# mainBord_real.net
KiCad netlist of a schematic drawn in Altium Designer
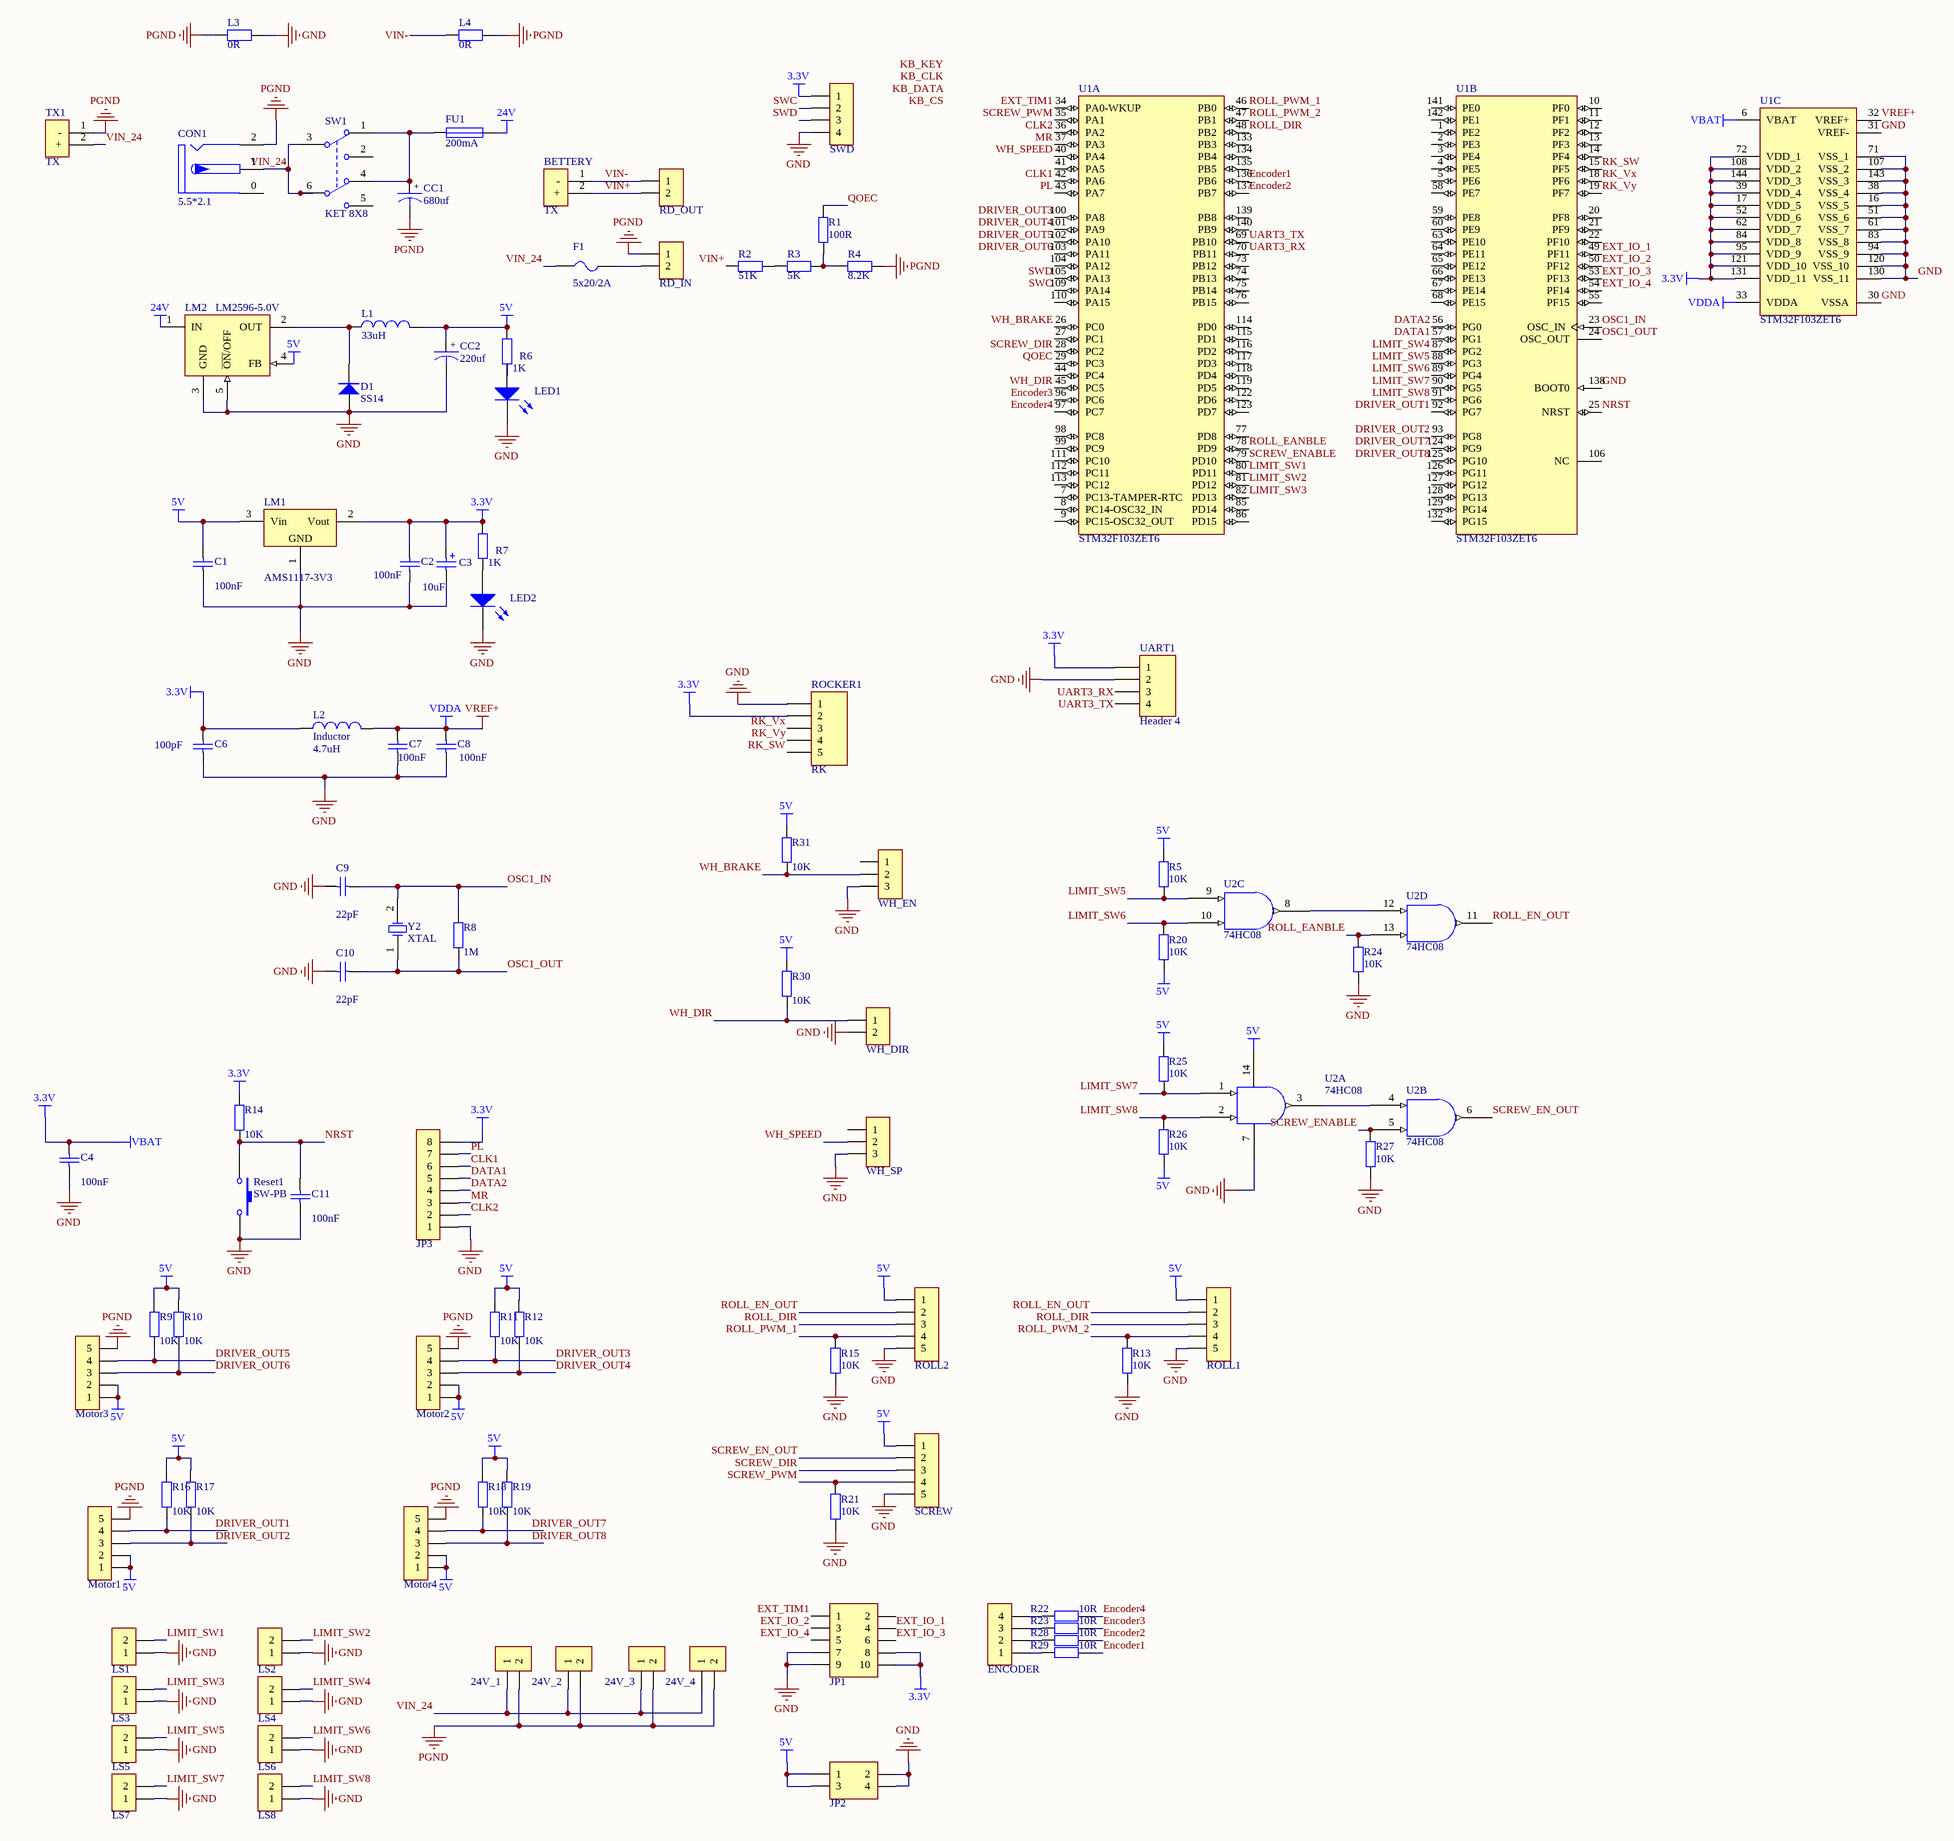
[diagram p0: mainBord_real.SchDoc]

(export (version "E")
  (design (tool "Eeschema 10.0.6"))
  (components
    (comp (ref "24V_1")
      (value "HDR-1X2")
      (footprint "KF2EDGK5.0-LI-2P")
      (description "2P接插件")
      (fields (field (name "版权归属") "源创客"))
      (libsource (lib "接插件") (part "Header 2"))
    )
    (comp (ref "24V_2")
      (value "HDR-1X2")
      (footprint "KF2EDGK5.0-LI-2P")
      (description "2P接插件")
      (fields (field (name "版权归属") "源创客"))
      (libsource (lib "接插件") (part "Header 2"))
    )
    (comp (ref "24V_3")
      (value "HDR-1X2")
      (footprint "KF2EDGK5.0-LI-2P")
      (description "2P接插件")
      (fields (field (name "版权归属") "源创客"))
      (libsource (lib "接插件") (part "Header 2"))
    )
    (comp (ref "24V_4")
      (value "HDR-1X2")
      (footprint "KF2EDGK5.0-LI-2P")
      (description "2P接插件")
      (fields (field (name "版权归属") "源创客"))
      (libsource (lib "接插件") (part "Header 2"))
    )
    (comp (ref "BETTERY") (value "TX") (footprint "TX") (libsource (lib "接头") (part "T型插头")))
    (comp (ref "C1")
      (value "100nF")
      (footprint "C 0805_L")
      (description "Capacitor")
      (fields (field (name "Comment") "100nf") (field (name "PUBLISHER") "Altium Limited"))
      (libsource (lib "Miscellaneous Devices") (part "Cap"))
    )
    (comp (ref "C2")
      (value "100nF")
      (footprint "C 0805_L")
      (description "Capacitor")
      (fields (field (name "Comment") "100nf") (field (name "PUBLISHER") "Altium Limited"))
      (libsource (lib "Miscellaneous Devices") (part "Cap"))
    )
    (comp (ref "C3")
      (value "10uF")
      (footprint "CD A(3216)")
      (description "Polarized Capacitor (Axial)")
      (fields (field (name "Comment") "10uf") (field (name "PUBLISHER") "Altium Limited"))
      (libsource (lib "Miscellaneous Devices") (part "Cap Pol2"))
    )
    (comp (ref "C4")
      (value "100nF")
      (footprint "C 0805_L")
      (description "Capacitor")
      (fields (field (name "Comment") "100nf") (field (name "PUBLISHER") "Altium Limited"))
      (libsource (lib "Miscellaneous Devices") (part "Cap"))
    )
    (comp (ref "C6")
      (value "100pF")
      (footprint "C 0805_L")
      (description "Capacitor")
      (fields (field (name "Comment") "100nf") (field (name "PUBLISHER") "Altium Limited"))
      (libsource (lib "Miscellaneous Devices") (part "Cap"))
    )
    (comp (ref "C7")
      (value "100nF")
      (footprint "C 0805_L")
      (description "Capacitor")
      (fields (field (name "Comment") "100nf") (field (name "PUBLISHER") "Altium Limited"))
      (libsource (lib "Miscellaneous Devices") (part "Cap"))
    )
    (comp (ref "C8")
      (value "100nF")
      (footprint "C 0805_L")
      (description "Capacitor")
      (fields (field (name "Comment") "100nf") (field (name "PUBLISHER") "Altium Limited"))
      (libsource (lib "Miscellaneous Devices") (part "Cap"))
    )
    (comp (ref "C9")
      (value "22pF")
      (footprint "C 0805_L")
      (description "Capacitor")
      (fields (field (name "Comment") "22pf") (field (name "PUBLISHER") "Altium Limited"))
      (libsource (lib "Miscellaneous Devices") (part "Cap"))
    )
    (comp (ref "C10")
      (value "22pF")
      (footprint "C 0805_L")
      (description "Capacitor")
      (fields (field (name "Comment") "22pf") (field (name "PUBLISHER") "Altium Limited"))
      (libsource (lib "Miscellaneous Devices") (part "Cap"))
    )
    (comp (ref "C11")
      (value "100nF")
      (footprint "C 0805_L")
      (description "Capacitor")
      (fields (field (name "Comment") "100nf") (field (name "PUBLISHER") "Altium Limited"))
      (libsource (lib "Miscellaneous Devices") (part "Cap"))
    )
    (comp (ref "CC1")
      (value "680uf")
      (footprint "CM F(10*10.2)")
      (description "贴片铝解电容")
      (libsource (lib "常用器件") (part "CAP-T"))
    )
    (comp (ref "CC2")
      (value "220uf")
      (footprint "CM E(8*10.2)")
      (description "贴片铝解电容")
      (libsource (lib "常用器件") (part "CAP-T"))
    )
    (comp (ref "CON1")
      (value "5.5*2.1")
      (footprint "DC-005")
      (description "带屏蔽DC电源接口")
      (fields (field (name "版权归属") "源创客"))
      (libsource (lib "4.1   - 接口类") (part "DC-005P"))
    )
    (comp (ref "D1")
      (value "SS14")
      (footprint "SMA")
      (description "肖特基二极管")
      (fields (field (name "版权归属") "源创客"))
      (libsource (lib "8.1   - 二极管-整流桥") (part "SS14"))
    )
    (comp (ref "ENCODER")
      (value "HDR-1X4")
      (footprint "HDR2.54-LI-4P")
      (description "4P接插件")
      (fields (field (name "版权归属") "源创客"))
      (libsource (lib "4.5   - 接插件-脚距2.54") (part "Header 4"))
    )
    (comp (ref "F1")
      (value "5x20/2A")
      (footprint "FU 5x20")
      (description "直插保险丝")
      (fields (field (name "版权归属") "源创客"))
      (libsource (lib "10.1 - 保险丝-晶振") (part "FU DIP"))
    )
    (comp (ref "FU1") (value "200mA") (footprint "R 1206-HP_M") (libsource (lib "常用器件") (part "FUSE")))
    (comp (ref "JP1")
      (value "Header 5X2")
      (footprint "HDR2.54-LI-2x5P")
      (description "5*2P接插件")
      (fields (field (name "版权归属") "源创客"))
      (libsource (lib "4.5   - 接插件-脚距2.54") (part "Header 5X2"))
    )
    (comp (ref "JP2")
      (value "Header2X2")
      (footprint "HDR2.54-LI-2x2P")
      (description "2*2P接插件")
      (fields (field (name "版权归属") "源创客"))
      (libsource (lib "4.5   - 接插件-脚距2.54") (part "Header 2X2"))
    )
    (comp (ref "JP3")
      (value "HDR-1X8")
      (footprint "XH2.54-LI-8P")
      (description "8P接插件")
      (fields (field (name "版权归属") "源创客"))
      (libsource (lib "4.5   - 接插件-脚距2.54") (part "Header 8"))
    )
    (comp (ref "L1")
      (value "33uH")
      (footprint "CDRH125")
      (description "Inductor")
      (fields
        (field (name "MANUFACTURER") "Generic Components")
        (field (name "PUBLISHER") "Altium Hobart Technology Centre")
      )
      (libsource (lib "常用器件") (part "Inductor"))
    )
    (comp (ref "L2")
      (value "Inductor")
      (footprint "L 0805")
      (fields (field (name "ALTIUM_VALUE") "4.7uH") (field (name "PUBLISHER") "Altium Limited"))
      (libsource (lib "Miscellaneous Devices") (part "Inductor"))
    )
    (comp (ref "L3")
      (value "0R")
      (footprint "R 0805_L")
      (description "Resistor")
      (fields (field (name "Comment") "1K") (field (name "PUBLISHER") "Altium Limited"))
      (libsource (lib "") (part "Res2_1"))
    )
    (comp (ref "L4")
      (value "0R")
      (footprint "R 0805_L")
      (description "Resistor")
      (fields (field (name "Comment") "1K") (field (name "PUBLISHER") "Altium Limited"))
      (libsource (lib "") (part "Res2_1"))
    )
    (comp (ref "LED1")
      (value "LED2")
      (footprint "LED 0805B")
      (description "Typical RED, GREEN, YELLOW, AMBER GaAs LED")
      (fields (field (name "PUBLISHER") "Altium Limited"))
      (libsource (lib "Miscellaneous Devices") (part "LED2"))
    )
    (comp (ref "LED2")
      (value "LED2")
      (footprint "LED 0805B")
      (description "Typical RED, GREEN, YELLOW, AMBER GaAs LED")
      (fields (field (name "PUBLISHER") "Altium Limited"))
      (libsource (lib "Miscellaneous Devices") (part "LED2"))
    )
    (comp (ref "LM1")
      (value "AMS1117-3V3")
      (footprint "SOT223_L")
      (description "三端稳压芯片")
      (fields (field (name "版权归属") "源创客"))
      (libsource (lib "1.3   - 电源类芯片") (part "AMS1117"))
    )
    (comp (ref "LM2")
      (value "LM2596-5.0V")
      (footprint "TO263-5A")
      (description "DC降压芯片")
      (fields (field (name "版权归属") "源创客"))
      (libsource (lib "1.3   - 电源类芯片") (part "LM2596-5.0"))
    )
    (comp (ref "LS1")
      (value "HDR-1X2")
      (footprint "XH2.54-LI-2P")
      (description "2P接插件")
      (fields (field (name "版权归属") "源创客"))
      (libsource (lib "4.5   - 接插件-脚距2.54") (part "Header 2"))
    )
    (comp (ref "LS2")
      (value "HDR-1X2")
      (footprint "XH2.54-LI-2P")
      (description "2P接插件")
      (fields (field (name "版权归属") "源创客"))
      (libsource (lib "4.5   - 接插件-脚距2.54") (part "Header 2"))
    )
    (comp (ref "LS3")
      (value "HDR-1X2")
      (footprint "XH2.54-LI-2P")
      (description "2P接插件")
      (fields (field (name "版权归属") "源创客"))
      (libsource (lib "4.5   - 接插件-脚距2.54") (part "Header 2"))
    )
    (comp (ref "LS4")
      (value "HDR-1X2")
      (footprint "XH2.54-LI-2P")
      (description "2P接插件")
      (fields (field (name "版权归属") "源创客"))
      (libsource (lib "4.5   - 接插件-脚距2.54") (part "Header 2"))
    )
    (comp (ref "LS5")
      (value "HDR-1X2")
      (footprint "XH2.54-LI-2P")
      (description "2P接插件")
      (fields (field (name "版权归属") "源创客"))
      (libsource (lib "4.5   - 接插件-脚距2.54") (part "Header 2"))
    )
    (comp (ref "LS6")
      (value "HDR-1X2")
      (footprint "XH2.54-LI-2P")
      (description "2P接插件")
      (fields (field (name "版权归属") "源创客"))
      (libsource (lib "4.5   - 接插件-脚距2.54") (part "Header 2"))
    )
    (comp (ref "LS7")
      (value "HDR-1X2")
      (footprint "XH2.54-LI-2P")
      (description "2P接插件")
      (fields (field (name "版权归属") "源创客"))
      (libsource (lib "4.5   - 接插件-脚距2.54") (part "Header 2"))
    )
    (comp (ref "LS8")
      (value "HDR-1X2")
      (footprint "XH2.54-LI-2P")
      (description "2P接插件")
      (fields (field (name "版权归属") "源创客"))
      (libsource (lib "4.5   - 接插件-脚距2.54") (part "Header 2"))
    )
    (comp (ref "Motor1")
      (value "HDR-1X5")
      (footprint "KF128-3.81-5P")
      (description "5P接插件")
      (fields (field (name "版权归属") "源创客"))
      (libsource (lib "接插件") (part "Header 5"))
    )
    (comp (ref "Motor2")
      (value "HDR-1X5")
      (footprint "KF128-3.81-5P")
      (description "5P接插件")
      (fields (field (name "版权归属") "源创客"))
      (libsource (lib "接插件") (part "Header 5"))
    )
    (comp (ref "Motor3")
      (value "HDR-1X5")
      (footprint "KF128-3.81-5P")
      (description "5P接插件")
      (fields (field (name "版权归属") "源创客"))
      (libsource (lib "接插件") (part "Header 5"))
    )
    (comp (ref "Motor4")
      (value "HDR-1X5")
      (footprint "KF128-3.81-5P")
      (description "5P接插件")
      (fields (field (name "版权归属") "源创客"))
      (libsource (lib "接插件") (part "Header 5"))
    )
    (comp (ref "R1")
      (value "100R")
      (footprint "R 0805_L")
      (description "Resistor")
      (fields (field (name "Comment") "1K") (field (name "PUBLISHER") "Altium Limited"))
      (libsource (lib "") (part "Res2_3"))
    )
    (comp (ref "R2")
      (value "51K")
      (footprint "R 0805_L")
      (description "Resistor")
      (fields (field (name "Comment") "1K") (field (name "PUBLISHER") "Altium Limited"))
      (libsource (lib "") (part "Res2_1"))
    )
    (comp (ref "R3")
      (value "5K")
      (footprint "R 0805_L")
      (description "Resistor")
      (fields (field (name "Comment") "1K") (field (name "PUBLISHER") "Altium Limited"))
      (libsource (lib "") (part "Res2_1"))
    )
    (comp (ref "R4")
      (value "8.2K")
      (footprint "R 0805_L")
      (description "Resistor")
      (fields (field (name "Comment") "1K") (field (name "PUBLISHER") "Altium Limited"))
      (libsource (lib "") (part "Res2_1"))
    )
    (comp (ref "R5")
      (value "10K")
      (footprint "R 0805_L")
      (description "Resistor")
      (fields (field (name "Comment") "5K") (field (name "PUBLISHER") "Altium Limited"))
      (libsource (lib "Miscellaneous Devices") (part "Res2"))
    )
    (comp (ref "R6")
      (value "1K")
      (footprint "R 0805_L")
      (description "Resistor")
      (fields (field (name "PUBLISHER") "Altium Limited"))
      (libsource (lib "Miscellaneous Devices") (part "Res2"))
    )
    (comp (ref "R7")
      (value "1K")
      (footprint "R 0805_L")
      (description "Resistor")
      (fields (field (name "PUBLISHER") "Altium Limited"))
      (libsource (lib "Miscellaneous Devices") (part "Res2"))
    )
    (comp (ref "R8")
      (value "1M")
      (footprint "R 0805_L")
      (description "Resistor")
      (fields (field (name "PUBLISHER") "Altium Limited"))
      (libsource (lib "Miscellaneous Devices") (part "Res2"))
    )
    (comp (ref "R9")
      (value "10K")
      (footprint "R 0805_L")
      (description "Resistor")
      (fields (field (name "Comment") "1K") (field (name "PUBLISHER") "Altium Limited"))
      (libsource (lib "Miscellaneous Devices") (part "Res2"))
    )
    (comp (ref "R10")
      (value "10K")
      (footprint "R 0805_L")
      (description "Resistor")
      (fields (field (name "Comment") "1K") (field (name "PUBLISHER") "Altium Limited"))
      (libsource (lib "Miscellaneous Devices") (part "Res2"))
    )
    (comp (ref "R11")
      (value "10K")
      (footprint "R 0805_L")
      (description "Resistor")
      (fields (field (name "Comment") "1K") (field (name "PUBLISHER") "Altium Limited"))
      (libsource (lib "Miscellaneous Devices") (part "Res2"))
    )
    (comp (ref "R12")
      (value "10K")
      (footprint "R 0805_L")
      (description "Resistor")
      (fields (field (name "Comment") "1K") (field (name "PUBLISHER") "Altium Limited"))
      (libsource (lib "Miscellaneous Devices") (part "Res2"))
    )
    (comp (ref "R13")
      (value "10K")
      (footprint "R 0805_L")
      (description "Resistor")
      (fields (field (name "Comment") "1K") (field (name "PUBLISHER") "Altium Limited"))
      (libsource (lib "") (part "Res2_3"))
    )
    (comp (ref "R14")
      (value "10K")
      (footprint "R 0805_L")
      (description "Resistor")
      (fields (field (name "Comment") "1K") (field (name "PUBLISHER") "Altium Limited"))
      (libsource (lib "Miscellaneous Devices") (part "Res2"))
    )
    (comp (ref "R15")
      (value "10K")
      (footprint "R 0805_L")
      (description "Resistor")
      (fields (field (name "Comment") "1K") (field (name "PUBLISHER") "Altium Limited"))
      (libsource (lib "") (part "Res2_3"))
    )
    (comp (ref "R16")
      (value "10K")
      (footprint "R 0805_L")
      (description "Resistor")
      (fields (field (name "Comment") "1K") (field (name "PUBLISHER") "Altium Limited"))
      (libsource (lib "Miscellaneous Devices") (part "Res2"))
    )
    (comp (ref "R17")
      (value "10K")
      (footprint "R 0805_L")
      (description "Resistor")
      (fields (field (name "Comment") "1K") (field (name "PUBLISHER") "Altium Limited"))
      (libsource (lib "Miscellaneous Devices") (part "Res2"))
    )
    (comp (ref "R18")
      (value "10K")
      (footprint "R 0805_L")
      (description "Resistor")
      (fields (field (name "Comment") "1K") (field (name "PUBLISHER") "Altium Limited"))
      (libsource (lib "Miscellaneous Devices") (part "Res2"))
    )
    (comp (ref "R19")
      (value "10K")
      (footprint "R 0805_L")
      (description "Resistor")
      (fields (field (name "Comment") "1K") (field (name "PUBLISHER") "Altium Limited"))
      (libsource (lib "Miscellaneous Devices") (part "Res2"))
    )
    (comp (ref "R20")
      (value "10K")
      (footprint "R 0805_L")
      (description "Resistor")
      (fields (field (name "Comment") "5K") (field (name "PUBLISHER") "Altium Limited"))
      (libsource (lib "Miscellaneous Devices") (part "Res2"))
    )
    (comp (ref "R21")
      (value "10K")
      (footprint "R 0805_L")
      (description "Resistor")
      (fields (field (name "Comment") "1K") (field (name "PUBLISHER") "Altium Limited"))
      (libsource (lib "") (part "Res2_3"))
    )
    (comp (ref "R22")
      (value "10R")
      (footprint "R 0805_L")
      (description "Resistor")
      (fields (field (name "Comment") "1K") (field (name "PUBLISHER") "Altium Limited"))
      (libsource (lib "") (part "Res2_2"))
    )
    (comp (ref "R23")
      (value "10R")
      (footprint "R 0805_L")
      (description "Resistor")
      (fields (field (name "Comment") "1K") (field (name "PUBLISHER") "Altium Limited"))
      (libsource (lib "") (part "Res2_2"))
    )
    (comp (ref "R24")
      (value "10K")
      (footprint "R 0805_L")
      (description "Resistor")
      (fields (field (name "Comment") "1K") (field (name "PUBLISHER") "Altium Limited"))
      (libsource (lib "Miscellaneous Devices") (part "Res2"))
    )
    (comp (ref "R25")
      (value "10K")
      (footprint "R 0805_L")
      (description "Resistor")
      (fields (field (name "Comment") "5K") (field (name "PUBLISHER") "Altium Limited"))
      (libsource (lib "Miscellaneous Devices") (part "Res2"))
    )
    (comp (ref "R26")
      (value "10K")
      (footprint "R 0805_L")
      (description "Resistor")
      (fields (field (name "Comment") "5K") (field (name "PUBLISHER") "Altium Limited"))
      (libsource (lib "Miscellaneous Devices") (part "Res2"))
    )
    (comp (ref "R27")
      (value "10K")
      (footprint "R 0805_L")
      (description "Resistor")
      (fields (field (name "Comment") "1K") (field (name "PUBLISHER") "Altium Limited"))
      (libsource (lib "Miscellaneous Devices") (part "Res2"))
    )
    (comp (ref "R28")
      (value "10R")
      (footprint "R 0805_L")
      (description "Resistor")
      (fields (field (name "Comment") "1K") (field (name "PUBLISHER") "Altium Limited"))
      (libsource (lib "") (part "Res2_2"))
    )
    (comp (ref "R29")
      (value "10R")
      (footprint "R 0805_L")
      (description "Resistor")
      (fields (field (name "Comment") "1K") (field (name "PUBLISHER") "Altium Limited"))
      (libsource (lib "") (part "Res2_2"))
    )
    (comp (ref "R30")
      (value "10K")
      (footprint "R 0805_L")
      (description "Resistor")
      (fields (field (name "Comment") "1K") (field (name "PUBLISHER") "Altium Limited"))
      (libsource (lib "Miscellaneous Devices") (part "Res2"))
    )
    (comp (ref "R31")
      (value "10K")
      (footprint "R 0805_L")
      (description "Resistor")
      (fields (field (name "Comment") "1K") (field (name "PUBLISHER") "Altium Limited"))
      (libsource (lib "Miscellaneous Devices") (part "Res2"))
    )
    (comp (ref "RD_IN")
      (value "HDR-1X2")
      (footprint "KF2EDGK5.0-WI-2P")
      (description "2P接插件")
      (fields (field (name "版权归属") "源创客"))
      (libsource (lib "") (part "Header 2_1"))
    )
    (comp (ref "RD_OUT")
      (value "HDR-1X2")
      (footprint "KF2EDGK5.0-WI-2P")
      (description "2P接插件")
      (fields (field (name "版权归属") "源创客"))
      (libsource (lib "") (part "Header 2_1"))
    )
    (comp (ref "Reset1")
      (value "SW-PB")
      (footprint "switch_1")
      (description "Switch")
      (fields (field (name "PUBLISHER") "Altium Limited"))
      (libsource (lib "Miscellaneous Devices") (part "SW-PB"))
    )
    (comp (ref "ROCKER1")
      (value "RK")
      (footprint "HDR2.54-M-LI-5P")
      (description "Header, 5-Pin")
      (fields (field (name "PUBLISHER") "Altium Limited"))
      (libsource (lib "Miscellaneous Connectors") (part "MHDR1X5"))
    )
    (comp (ref "ROLL1")
      (value "HDR-1X5")
      (footprint "XH2.54-LI-5P")
      (description "5P接插件")
      (fields (field (name "版权归属") "源创客"))
      (libsource (lib "4.5   - 接插件-脚距2.54") (part "Header 5"))
    )
    (comp (ref "ROLL2")
      (value "HDR-1X5")
      (footprint "XH2.54-LI-5P")
      (description "5P接插件")
      (fields (field (name "版权归属") "源创客"))
      (libsource (lib "4.5   - 接插件-脚距2.54") (part "Header 5"))
    )
    (comp (ref "SCREW")
      (value "HDR-1X5")
      (footprint "XH2.54-LI-5P")
      (description "5P接插件")
      (fields (field (name "版权归属") "源创客"))
      (libsource (lib "4.5   - 接插件-脚距2.54") (part "Header 5"))
    )
    (comp (ref "SW1")
      (value "KET 8X8")
      (footprint "KFT DIP-8X8")
      (description "8*8自锁开关")
      (fields (field (name "版权归属") "源创客"))
      (libsource (lib "5.1   - 按键-开关") (part "KET 8X8"))
    )
    (comp (ref "SWD")
      (value "HDR-1X4")
      (footprint "HDR2.54-LI-4P")
      (description "4P接插件")
      (fields (field (name "版权归属") "源创客"))
      (libsource (lib "") (part "Header 4_1"))
    )
    (comp (ref "TX1") (value "TX") (footprint "TX") (libsource (lib "接头") (part "T型插头")))
    (comp (ref "U1")
      (value "STM32F103ZET6")
      (footprint "STM-LQFP144_N")
      (libsource (lib "STMicroelectronics STM32 F1") (part "STM32F103ZET6"))
    )
    (comp (ref "U2") (value "74HC08") (footprint "SOP14_N") (libsource (lib "逻辑门器件") (part "74HC08")))
    (comp (ref "UART1")
      (value "Header 4")
      (footprint "HDR2.54-LI-4P")
      (description "Header, 4-Pin")
      (fields (field (name "PUBLISHER") "Altium Limited"))
      (libsource (lib "Miscellaneous Connectors") (part "Header 4"))
    )
    (comp (ref "WH_DIR")
      (value "HDR-1X2")
      (footprint "XH2.54-LI-2P")
      (description "2P接插件")
      (fields (field (name "版权归属") "源创客"))
      (libsource (lib "") (part "Header 2_1"))
    )
    (comp (ref "WH_EN")
      (value "HDR-1X3")
      (footprint "XH2.54-LI-3P")
      (description "3P接插件")
      (fields (field (name "版权归属") "源创客"))
      (libsource (lib "4.5   - 接插件-脚距2.54") (part "Header 3"))
    )
    (comp (ref "WH_SP")
      (value "HDR-1X3")
      (footprint "XH2.54-LI-3P")
      (description "3P接插件")
      (fields (field (name "版权归属") "源创客"))
      (libsource (lib "4.5   - 接插件-脚距2.54") (part "Header 3"))
    )
    (comp (ref "Y2")
      (value "XTAL")
      (footprint "OSC HC-49S")
      (description "Crystal Oscillator")
      (fields (field (name "PUBLISHER") "Altium Limited"))
      (libsource (lib "Miscellaneous Devices") (part "XTAL"))
    )
  )
  (nets
    (net (code "1") (name "/CLK1") (class "Default")
      (node (ref "JP3") (pin "6") (pinfunction "6_6") (pintype "passive"))
      (node (ref "U1") (pin "42") (pinfunction "PA6_42") (pintype "bidirectional"))
    )
    (net (code "2") (name "/CLK2") (class "Default")
      (node (ref "JP3") (pin "2") (pinfunction "2_2") (pintype "passive"))
      (node (ref "U1") (pin "36") (pinfunction "PA2_36") (pintype "bidirectional"))
    )
    (net (code "3") (name "/DATA1") (class "Default")
      (node (ref "JP3") (pin "5") (pinfunction "5_5") (pintype "passive"))
      (node (ref "U1") (pin "57") (pinfunction "PG1_57") (pintype "bidirectional"))
    )
    (net (code "4") (name "/DATA2") (class "Default")
      (node (ref "JP3") (pin "4") (pinfunction "4_4") (pintype "passive"))
      (node (ref "U1") (pin "56") (pinfunction "PG0_56") (pintype "bidirectional"))
    )
    (net (code "5") (name "/DRIVER_OUT1") (class "Default")
      (node (ref "Motor1") (pin "4") (pinfunction "4_4") (pintype "passive"))
      (node (ref "R16") (pin "1") (pinfunction "1_1") (pintype "passive"))
      (node (ref "U1") (pin "92") (pinfunction "PG7_92") (pintype "bidirectional"))
    )
    (net (code "6") (name "/DRIVER_OUT2") (class "Default")
      (node (ref "Motor1") (pin "3") (pinfunction "3_3") (pintype "passive"))
      (node (ref "R17") (pin "1") (pinfunction "1_1") (pintype "passive"))
      (node (ref "U1") (pin "93") (pinfunction "PG8_93") (pintype "bidirectional"))
    )
    (net (code "7") (name "/DRIVER_OUT3") (class "Default")
      (node (ref "Motor2") (pin "4") (pinfunction "4_4") (pintype "passive"))
      (node (ref "R11") (pin "1") (pinfunction "1_1") (pintype "passive"))
      (node (ref "U1") (pin "100") (pinfunction "PA8_100") (pintype "bidirectional"))
    )
    (net (code "8") (name "/DRIVER_OUT4") (class "Default")
      (node (ref "Motor2") (pin "3") (pinfunction "3_3") (pintype "passive"))
      (node (ref "R12") (pin "1") (pinfunction "1_1") (pintype "passive"))
      (node (ref "U1") (pin "101") (pinfunction "PA9_101") (pintype "bidirectional"))
    )
    (net (code "9") (name "/DRIVER_OUT5") (class "Default")
      (node (ref "Motor3") (pin "4") (pinfunction "4_4") (pintype "passive"))
      (node (ref "R9") (pin "1") (pinfunction "1_1") (pintype "passive"))
      (node (ref "U1") (pin "102") (pinfunction "PA10_102") (pintype "bidirectional"))
    )
    (net (code "10") (name "/DRIVER_OUT6") (class "Default")
      (node (ref "Motor3") (pin "3") (pinfunction "3_3") (pintype "passive"))
      (node (ref "R10") (pin "1") (pinfunction "1_1") (pintype "passive"))
      (node (ref "U1") (pin "103") (pinfunction "PA11_103") (pintype "bidirectional"))
    )
    (net (code "11") (name "/DRIVER_OUT7") (class "Default")
      (node (ref "Motor4") (pin "4") (pinfunction "4_4") (pintype "passive"))
      (node (ref "R18") (pin "1") (pinfunction "1_1") (pintype "passive"))
      (node (ref "U1") (pin "124") (pinfunction "PG9_124") (pintype "bidirectional"))
    )
    (net (code "12") (name "/DRIVER_OUT8") (class "Default")
      (node (ref "Motor4") (pin "3") (pinfunction "3_3") (pintype "passive"))
      (node (ref "R19") (pin "1") (pinfunction "1_1") (pintype "passive"))
      (node (ref "U1") (pin "125") (pinfunction "PG10_125") (pintype "bidirectional"))
    )
    (net (code "13") (name "/EXT_IO_1") (class "Default")
      (node (ref "JP1") (pin "4") (pinfunction "4_4") (pintype "passive"))
      (node (ref "U1") (pin "49") (pinfunction "PF11_49") (pintype "bidirectional"))
    )
    (net (code "14") (name "/EXT_IO_2") (class "Default")
      (node (ref "JP1") (pin "3") (pinfunction "3_3") (pintype "passive"))
      (node (ref "U1") (pin "50") (pinfunction "PF12_50") (pintype "bidirectional"))
    )
    (net (code "15") (name "/EXT_IO_3") (class "Default")
      (node (ref "JP1") (pin "6") (pinfunction "6_6") (pintype "passive"))
      (node (ref "U1") (pin "53") (pinfunction "PF13_53") (pintype "bidirectional"))
    )
    (net (code "16") (name "/EXT_IO_4") (class "Default")
      (node (ref "JP1") (pin "5") (pinfunction "5_5") (pintype "passive"))
      (node (ref "U1") (pin "54") (pinfunction "PF14_54") (pintype "bidirectional"))
    )
    (net (code "17") (name "/EXT_TIM1") (class "Default")
      (node (ref "JP1") (pin "1") (pinfunction "1_1") (pintype "passive"))
      (node (ref "U1") (pin "34") (pinfunction "PA0-WKUP_34") (pintype "bidirectional"))
    )
    (net (code "18") (name "/Encoder1") (class "Default")
      (node (ref "R29") (pin "2") (pinfunction "2_2") (pintype "passive"))
      (node (ref "U1") (pin "136") (pinfunction "PB6_136") (pintype "bidirectional"))
    )
    (net (code "19") (name "/Encoder2") (class "Default")
      (node (ref "R28") (pin "2") (pinfunction "2_2") (pintype "passive"))
      (node (ref "U1") (pin "137") (pinfunction "PB7_137") (pintype "bidirectional"))
    )
    (net (code "20") (name "/Encoder3") (class "Default")
      (node (ref "R23") (pin "2") (pinfunction "2_2") (pintype "passive"))
      (node (ref "U1") (pin "96") (pinfunction "PC6_96") (pintype "bidirectional"))
    )
    (net (code "21") (name "/Encoder4") (class "Default")
      (node (ref "R22") (pin "2") (pinfunction "2_2") (pintype "passive"))
      (node (ref "U1") (pin "97") (pinfunction "PC7_97") (pintype "bidirectional"))
    )
    (net (code "26") (name "/LIMIT_SW1") (class "Default")
      (node (ref "LS1") (pin "2") (pinfunction "2_2") (pintype "passive"))
      (node (ref "U1") (pin "80") (pinfunction "PD11_80") (pintype "bidirectional"))
    )
    (net (code "27") (name "/LIMIT_SW2") (class "Default")
      (node (ref "LS2") (pin "2") (pinfunction "2_2") (pintype "passive"))
      (node (ref "U1") (pin "81") (pinfunction "PD12_81") (pintype "bidirectional"))
    )
    (net (code "28") (name "/LIMIT_SW3") (class "Default")
      (node (ref "LS3") (pin "2") (pinfunction "2_2") (pintype "passive"))
      (node (ref "U1") (pin "82") (pinfunction "PD13_82") (pintype "bidirectional"))
    )
    (net (code "29") (name "/LIMIT_SW4") (class "Default")
      (node (ref "LS4") (pin "2") (pinfunction "2_2") (pintype "passive"))
      (node (ref "U1") (pin "87") (pinfunction "PG2_87") (pintype "bidirectional"))
    )
    (net (code "30") (name "/LIMIT_SW5") (class "Default")
      (node (ref "LS5") (pin "2") (pinfunction "2_2") (pintype "passive"))
      (node (ref "R5") (pin "1") (pinfunction "1_1") (pintype "passive"))
      (node (ref "U1") (pin "88") (pinfunction "PG3_88") (pintype "bidirectional"))
      (node (ref "U2") (pin "9") (pintype "input"))
    )
    (net (code "31") (name "/LIMIT_SW6") (class "Default")
      (node (ref "LS6") (pin "2") (pinfunction "2_2") (pintype "passive"))
      (node (ref "R20") (pin "2") (pinfunction "2_2") (pintype "passive"))
      (node (ref "U1") (pin "89") (pinfunction "PG4_89") (pintype "bidirectional"))
      (node (ref "U2") (pin "10") (pintype "input"))
    )
    (net (code "32") (name "/LIMIT_SW7") (class "Default")
      (node (ref "LS7") (pin "2") (pinfunction "2_2") (pintype "passive"))
      (node (ref "R25") (pin "1") (pinfunction "1_1") (pintype "passive"))
      (node (ref "U1") (pin "90") (pinfunction "PG5_90") (pintype "bidirectional"))
      (node (ref "U2") (pin "1") (pintype "input"))
    )
    (net (code "33") (name "/LIMIT_SW8") (class "Default")
      (node (ref "LS8") (pin "2") (pinfunction "2_2") (pintype "passive"))
      (node (ref "R26") (pin "2") (pinfunction "2_2") (pintype "passive"))
      (node (ref "U1") (pin "91") (pinfunction "PG6_91") (pintype "bidirectional"))
      (node (ref "U2") (pin "2") (pintype "input"))
    )
    (net (code "34") (name "/MR") (class "Default")
      (node (ref "JP3") (pin "3") (pinfunction "3_3") (pintype "passive"))
      (node (ref "U1") (pin "37") (pinfunction "PA3_37") (pintype "bidirectional"))
    )
    (net (code "35") (name "/NRST") (class "Default")
      (node (ref "C11") (pin "1") (pinfunction "1_1") (pintype "passive"))
      (node (ref "R14") (pin "1") (pinfunction "1_1") (pintype "passive"))
      (node (ref "Reset1") (pin "1") (pinfunction "1_1") (pintype "passive"))
      (node (ref "U1") (pin "25") (pinfunction "NRST_25") (pintype "bidirectional"))
    )
    (net (code "36") (name "/OSC1_IN") (class "Default")
      (node (ref "C9") (pin "1") (pinfunction "1_1") (pintype "passive"))
      (node (ref "R8") (pin "2") (pinfunction "2_2") (pintype "passive"))
      (node (ref "U1") (pin "23") (pinfunction "OSC_IN_23") (pintype "input"))
      (node (ref "Y2") (pin "2") (pinfunction "OSC2_2") (pintype "passive"))
    )
    (net (code "37") (name "/OSC1_OUT") (class "Default")
      (node (ref "C10") (pin "1") (pinfunction "1_1") (pintype "passive"))
      (node (ref "R8") (pin "1") (pinfunction "1_1") (pintype "passive"))
      (node (ref "U1") (pin "24") (pinfunction "OSC_OUT_24") (pintype "passive"))
      (node (ref "Y2") (pin "1") (pinfunction "OSC1_1") (pintype "passive"))
    )
    (net (code "38") (name "/PL") (class "Default")
      (node (ref "JP3") (pin "7") (pinfunction "7_7") (pintype "passive"))
      (node (ref "U1") (pin "43") (pinfunction "PA7_43") (pintype "bidirectional"))
    )
    (net (code "39") (name "/QOEC") (class "Default")
      (node (ref "R1") (pin "1") (pinfunction "1_1") (pintype "passive"))
      (node (ref "U1") (pin "29") (pinfunction "PC3_29") (pintype "bidirectional"))
    )
    (net (code "40") (name "/RK_SW") (class "Default")
      (node (ref "ROCKER1") (pin "5") (pinfunction "5_5") (pintype "passive"))
      (node (ref "U1") (pin "15") (pinfunction "PF5_15") (pintype "bidirectional"))
    )
    (net (code "41") (name "/RK_Vx") (class "Default")
      (node (ref "ROCKER1") (pin "3") (pinfunction "3_3") (pintype "passive"))
      (node (ref "U1") (pin "18") (pinfunction "PF6_18") (pintype "bidirectional"))
    )
    (net (code "42") (name "/RK_Vy") (class "Default")
      (node (ref "ROCKER1") (pin "4") (pinfunction "4_4") (pintype "passive"))
      (node (ref "U1") (pin "19") (pinfunction "PF7_19") (pintype "bidirectional"))
    )
    (net (code "43") (name "/ROLL_DIR") (class "Default")
      (node (ref "ROLL1") (pin "3") (pinfunction "3_3") (pintype "passive"))
      (node (ref "ROLL2") (pin "3") (pinfunction "3_3") (pintype "passive"))
      (node (ref "U1") (pin "48") (pinfunction "PB2_48") (pintype "bidirectional"))
    )
    (net (code "44") (name "/ROLL_EANBLE") (class "Default")
      (node (ref "R24") (pin "2") (pinfunction "2_2") (pintype "passive"))
      (node (ref "U1") (pin "78") (pinfunction "PD9_78") (pintype "bidirectional"))
      (node (ref "U2") (pin "13") (pintype "input"))
    )
    (net (code "45") (name "/ROLL_EN_OUT") (class "Default")
      (node (ref "ROLL1") (pin "2") (pinfunction "2_2") (pintype "passive"))
      (node (ref "ROLL2") (pin "2") (pinfunction "2_2") (pintype "passive"))
      (node (ref "U2") (pin "11") (pintype "output"))
    )
    (net (code "46") (name "/ROLL_PWM_1") (class "Default")
      (node (ref "R15") (pin "1") (pinfunction "1_1") (pintype "passive"))
      (node (ref "ROLL2") (pin "4") (pinfunction "4_4") (pintype "passive"))
      (node (ref "U1") (pin "46") (pinfunction "PB0_46") (pintype "bidirectional"))
    )
    (net (code "47") (name "/ROLL_PWM_2") (class "Default")
      (node (ref "R13") (pin "1") (pinfunction "1_1") (pintype "passive"))
      (node (ref "ROLL1") (pin "4") (pinfunction "4_4") (pintype "passive"))
      (node (ref "U1") (pin "47") (pinfunction "PB1_47") (pintype "bidirectional"))
    )
    (net (code "48") (name "/SCREW_DIR") (class "Default")
      (node (ref "SCREW") (pin "3") (pinfunction "3_3") (pintype "passive"))
      (node (ref "U1") (pin "28") (pinfunction "PC2_28") (pintype "bidirectional"))
    )
    (net (code "49") (name "/SCREW_ENABLE") (class "Default")
      (node (ref "R27") (pin "2") (pinfunction "2_2") (pintype "passive"))
      (node (ref "U1") (pin "79") (pinfunction "PD10_79") (pintype "bidirectional"))
      (node (ref "U2") (pin "5") (pintype "input"))
    )
    (net (code "50") (name "/SCREW_EN_OUT") (class "Default")
      (node (ref "SCREW") (pin "2") (pinfunction "2_2") (pintype "passive"))
      (node (ref "U2") (pin "6") (pintype "output"))
    )
    (net (code "51") (name "/SCREW_PWM") (class "Default")
      (node (ref "R21") (pin "1") (pinfunction "1_1") (pintype "passive"))
      (node (ref "SCREW") (pin "4") (pinfunction "4_4") (pintype "passive"))
      (node (ref "U1") (pin "35") (pinfunction "PA1_35") (pintype "bidirectional"))
    )
    (net (code "52") (name "/SWC") (class "Default")
      (node (ref "SWD") (pin "2") (pinfunction "2_2") (pintype "passive"))
      (node (ref "U1") (pin "109") (pinfunction "PA14_109") (pintype "bidirectional"))
    )
    (net (code "53") (name "/SWD") (class "Default")
      (node (ref "SWD") (pin "3") (pinfunction "3_3") (pintype "passive"))
      (node (ref "U1") (pin "105") (pinfunction "PA13_105") (pintype "bidirectional"))
    )
    (net (code "54") (name "/UART3_RX") (class "Default")
      (node (ref "U1") (pin "70") (pinfunction "PB11_70") (pintype "bidirectional"))
      (node (ref "UART1") (pin "3") (pinfunction "3_3") (pintype "passive"))
    )
    (net (code "55") (name "/UART3_TX") (class "Default")
      (node (ref "U1") (pin "69") (pinfunction "PB10_69") (pintype "bidirectional"))
      (node (ref "UART1") (pin "4") (pinfunction "4_4") (pintype "passive"))
    )
    (net (code "56") (name "/VIN+") (class "Default")
      (node (ref "BETTERY") (pin "2") (pinfunction "+_2") (pintype "passive"))
      (node (ref "R2") (pin "2") (pinfunction "2_2") (pintype "passive"))
      (node (ref "RD_OUT") (pin "2") (pinfunction "2_2") (pintype "passive"))
    )
    (net (code "57") (name "/VIN-") (class "Default")
      (node (ref "BETTERY") (pin "1") (pinfunction "-_1") (pintype "passive"))
      (node (ref "L4") (pin "2") (pinfunction "2_2") (pintype "passive"))
      (node (ref "RD_OUT") (pin "1") (pinfunction "1_1") (pintype "passive"))
    )
    (net (code "58") (name "/VIN_24") (class "Default")
      (node (ref "24V_1") (pin "1") (pinfunction "1_1") (pintype "passive"))
      (node (ref "24V_2") (pin "1") (pinfunction "1_1") (pintype "passive"))
      (node (ref "24V_3") (pin "1") (pinfunction "1_1") (pintype "passive"))
      (node (ref "24V_4") (pin "1") (pinfunction "1_1") (pintype "passive"))
      (node (ref "CON1") (pin "1") (pintype "power_in"))
      (node (ref "F1") (pin "2") (pinfunction "2_2") (pintype "passive"))
      (node (ref "SW1") (pin "3") (pinfunction "NO1_3") (pintype "passive"))
      (node (ref "SW1") (pin "6") (pinfunction "NC2_6") (pintype "passive"))
      (node (ref "TX1") (pin "2") (pinfunction "+_2") (pintype "passive"))
    )
    (net (code "59") (name "/WH_BRAKE") (class "Default")
      (node (ref "R31") (pin "1") (pinfunction "1_1") (pintype "passive"))
      (node (ref "U1") (pin "26") (pinfunction "PC0_26") (pintype "bidirectional"))
      (node (ref "WH_EN") (pin "2") (pinfunction "2_2") (pintype "passive"))
    )
    (net (code "60") (name "/WH_DIR") (class "Default")
      (node (ref "R30") (pin "1") (pinfunction "1_1") (pintype "passive"))
      (node (ref "U1") (pin "45") (pinfunction "PC5_45") (pintype "bidirectional"))
      (node (ref "WH_DIR") (pin "1") (pinfunction "1_1") (pintype "passive"))
    )
    (net (code "61") (name "/WH_SPEED") (class "Default")
      (node (ref "U1") (pin "40") (pinfunction "PA4_40") (pintype "bidirectional"))
      (node (ref "WH_SP") (pin "2") (pinfunction "2_2") (pintype "passive"))
    )
    (net (code "62") (name "3.3V") (class "Default")
      (node (ref "C2") (pin "2") (pinfunction "2_2") (pintype "passive"))
      (node (ref "C3") (pin "1") (pinfunction "1_1") (pintype "passive"))
      (node (ref "C4") (pin "1") (pinfunction "1_1") (pintype "passive"))
      (node (ref "C6") (pin "2") (pinfunction "2_2") (pintype "passive"))
      (node (ref "JP1") (pin "10") (pinfunction "10_10") (pintype "passive"))
      (node (ref "JP1") (pin "8") (pinfunction "8_8") (pintype "passive"))
      (node (ref "JP3") (pin "8") (pinfunction "8_8") (pintype "passive"))
      (node (ref "L2") (pin "1") (pinfunction "1_1") (pintype "passive"))
      (node (ref "LM1") (pin "2") (pinfunction "Vout_2") (pintype "passive"))
      (node (ref "R14") (pin "2") (pinfunction "2_2") (pintype "passive"))
      (node (ref "R7") (pin "2") (pinfunction "2_2") (pintype "passive"))
      (node (ref "ROCKER1") (pin "2") (pinfunction "2_2") (pintype "passive"))
      (node (ref "SWD") (pin "1") (pinfunction "1_1") (pintype "passive"))
      (node (ref "U1") (pin "108") (pinfunction "VDD_2_108") (pintype "power_in"))
      (node (ref "U1") (pin "121") (pinfunction "VDD_10_121") (pintype "power_in"))
      (node (ref "U1") (pin "131") (pinfunction "VDD_11_131") (pintype "power_in"))
      (node (ref "U1") (pin "144") (pinfunction "VDD_3_144") (pintype "power_in"))
      (node (ref "U1") (pin "17") (pinfunction "VDD_5_17") (pintype "power_in"))
      (node (ref "U1") (pin "39") (pinfunction "VDD_4_39") (pintype "power_in"))
      (node (ref "U1") (pin "52") (pinfunction "VDD_6_52") (pintype "power_in"))
      (node (ref "U1") (pin "6") (pinfunction "VBAT_6") (pintype "power_in"))
      (node (ref "U1") (pin "62") (pinfunction "VDD_7_62") (pintype "power_in"))
      (node (ref "U1") (pin "72") (pinfunction "VDD_1_72") (pintype "power_in"))
      (node (ref "U1") (pin "84") (pinfunction "VDD_8_84") (pintype "power_in"))
      (node (ref "U1") (pin "95") (pinfunction "VDD_9_95") (pintype "power_in"))
      (node (ref "UART1") (pin "1") (pinfunction "1_1") (pintype "passive"))
    )
    (net (code "63") (name "5V") (class "Default")
      (node (ref "C1") (pin "2") (pinfunction "2_2") (pintype "passive"))
      (node (ref "CC2") (pin "1") (pinfunction "1_1") (pintype "passive"))
      (node (ref "JP2") (pin "1") (pinfunction "1_1") (pintype "passive"))
      (node (ref "JP2") (pin "3") (pinfunction "3_3") (pintype "passive"))
      (node (ref "L1") (pin "2") (pinfunction "2_2") (pintype "passive"))
      (node (ref "LM1") (pin "3") (pinfunction "Vin_3") (pintype "passive"))
      (node (ref "LM2") (pin "4") (pinfunction "FB_4") (pintype "input"))
      (node (ref "Motor1") (pin "1") (pinfunction "1_1") (pintype "passive"))
      (node (ref "Motor1") (pin "2") (pinfunction "2_2") (pintype "passive"))
      (node (ref "Motor2") (pin "1") (pinfunction "1_1") (pintype "passive"))
      (node (ref "Motor2") (pin "2") (pinfunction "2_2") (pintype "passive"))
      (node (ref "Motor3") (pin "1") (pinfunction "1_1") (pintype "passive"))
      (node (ref "Motor3") (pin "2") (pinfunction "2_2") (pintype "passive"))
      (node (ref "Motor4") (pin "1") (pinfunction "1_1") (pintype "passive"))
      (node (ref "Motor4") (pin "2") (pinfunction "2_2") (pintype "passive"))
      (node (ref "R10") (pin "2") (pinfunction "2_2") (pintype "passive"))
      (node (ref "R11") (pin "2") (pinfunction "2_2") (pintype "passive"))
      (node (ref "R12") (pin "2") (pinfunction "2_2") (pintype "passive"))
      (node (ref "R16") (pin "2") (pinfunction "2_2") (pintype "passive"))
      (node (ref "R17") (pin "2") (pinfunction "2_2") (pintype "passive"))
      (node (ref "R18") (pin "2") (pinfunction "2_2") (pintype "passive"))
      (node (ref "R19") (pin "2") (pinfunction "2_2") (pintype "passive"))
      (node (ref "R20") (pin "1") (pinfunction "1_1") (pintype "passive"))
      (node (ref "R25") (pin "2") (pinfunction "2_2") (pintype "passive"))
      (node (ref "R26") (pin "1") (pinfunction "1_1") (pintype "passive"))
      (node (ref "R30") (pin "2") (pinfunction "2_2") (pintype "passive"))
      (node (ref "R31") (pin "2") (pinfunction "2_2") (pintype "passive"))
      (node (ref "R5") (pin "2") (pinfunction "2_2") (pintype "passive"))
      (node (ref "R6") (pin "2") (pinfunction "2_2") (pintype "passive"))
      (node (ref "R9") (pin "2") (pinfunction "2_2") (pintype "passive"))
      (node (ref "ROLL1") (pin "1") (pinfunction "1_1") (pintype "passive"))
      (node (ref "ROLL2") (pin "1") (pinfunction "1_1") (pintype "passive"))
      (node (ref "SCREW") (pin "1") (pinfunction "1_1") (pintype "passive"))
      (node (ref "U2") (pin "14") (pinfunction "VCC_14") (pintype "power_in"))
    )
    (net (code "64") (name "24V") (class "Default")
      (node (ref "FU1") (pin "2") (pinfunction "2_2") (pintype "passive"))
      (node (ref "LM2") (pin "1") (pinfunction "IN_1") (pintype "power_in"))
    )
    (net (code "65") (name "GND") (class "Default")
      (node (ref "C1") (pin "1") (pinfunction "1_1") (pintype "passive"))
      (node (ref "C10") (pin "2") (pinfunction "2_2") (pintype "passive"))
      (node (ref "C11") (pin "2") (pinfunction "2_2") (pintype "passive"))
      (node (ref "C2") (pin "1") (pinfunction "1_1") (pintype "passive"))
      (node (ref "C3") (pin "2") (pinfunction "2_2") (pintype "passive"))
      (node (ref "C4") (pin "2") (pinfunction "2_2") (pintype "passive"))
      (node (ref "C6") (pin "1") (pinfunction "1_1") (pintype "passive"))
      (node (ref "C7") (pin "1") (pinfunction "1_1") (pintype "passive"))
      (node (ref "C8") (pin "1") (pinfunction "1_1") (pintype "passive"))
      (node (ref "C9") (pin "2") (pinfunction "2_2") (pintype "passive"))
      (node (ref "CC2") (pin "2") (pinfunction "2_2") (pintype "passive"))
      (node (ref "D1") (pin "1") (pinfunction "A_1") (pintype "passive"))
      (node (ref "JP1") (pin "7") (pinfunction "7_7") (pintype "passive"))
      (node (ref "JP1") (pin "9") (pinfunction "9_9") (pintype "passive"))
      (node (ref "JP2") (pin "2") (pinfunction "2_2") (pintype "passive"))
      (node (ref "JP2") (pin "4") (pinfunction "4_4") (pintype "passive"))
      (node (ref "JP3") (pin "1") (pinfunction "1_1") (pintype "passive"))
      (node (ref "L3") (pin "1") (pinfunction "1_1") (pintype "passive"))
      (node (ref "LED1") (pin "2") (pinfunction "K_2") (pintype "passive"))
      (node (ref "LED2") (pin "2") (pinfunction "K_2") (pintype "passive"))
      (node (ref "LM1") (pin "1") (pinfunction "GND_1") (pintype "passive"))
      (node (ref "LM2") (pin "3") (pinfunction "GND_3") (pintype "power_in"))
      (node (ref "LM2") (pin "5") (pinfunction "~{ON}/OFF_5") (pintype "input"))
      (node (ref "LS1") (pin "1") (pinfunction "1_1") (pintype "passive"))
      (node (ref "LS2") (pin "1") (pinfunction "1_1") (pintype "passive"))
      (node (ref "LS3") (pin "1") (pinfunction "1_1") (pintype "passive"))
      (node (ref "LS4") (pin "1") (pinfunction "1_1") (pintype "passive"))
      (node (ref "LS5") (pin "1") (pinfunction "1_1") (pintype "passive"))
      (node (ref "LS6") (pin "1") (pinfunction "1_1") (pintype "passive"))
      (node (ref "LS7") (pin "1") (pinfunction "1_1") (pintype "passive"))
      (node (ref "LS8") (pin "1") (pinfunction "1_1") (pintype "passive"))
      (node (ref "R13") (pin "2") (pinfunction "2_2") (pintype "passive"))
      (node (ref "R15") (pin "2") (pinfunction "2_2") (pintype "passive"))
      (node (ref "R21") (pin "2") (pinfunction "2_2") (pintype "passive"))
      (node (ref "R24") (pin "1") (pinfunction "1_1") (pintype "passive"))
      (node (ref "R27") (pin "1") (pinfunction "1_1") (pintype "passive"))
      (node (ref "ROCKER1") (pin "1") (pinfunction "1_1") (pintype "passive"))
      (node (ref "ROLL1") (pin "5") (pinfunction "5_5") (pintype "passive"))
      (node (ref "ROLL2") (pin "5") (pinfunction "5_5") (pintype "passive"))
      (node (ref "Reset1") (pin "2") (pinfunction "2_2") (pintype "passive"))
      (node (ref "SCREW") (pin "5") (pinfunction "5_5") (pintype "passive"))
      (node (ref "SWD") (pin "4") (pinfunction "4_4") (pintype "passive"))
      (node (ref "U1") (pin "107") (pinfunction "VSS_2_107") (pintype "power_in"))
      (node (ref "U1") (pin "120") (pinfunction "VSS_10_120") (pintype "power_in"))
      (node (ref "U1") (pin "130") (pinfunction "VSS_11_130") (pintype "power_in"))
      (node (ref "U1") (pin "138") (pinfunction "BOOT0_138") (pintype "input"))
      (node (ref "U1") (pin "143") (pinfunction "VSS_3_143") (pintype "power_in"))
      (node (ref "U1") (pin "16") (pinfunction "VSS_5_16") (pintype "power_in"))
      (node (ref "U1") (pin "30") (pinfunction "VSSA_30") (pintype "power_in"))
      (node (ref "U1") (pin "31") (pinfunction "VREF-_31") (pintype "power_in"))
      (node (ref "U1") (pin "38") (pinfunction "VSS_4_38") (pintype "power_in"))
      (node (ref "U1") (pin "51") (pinfunction "VSS_6_51") (pintype "power_in"))
      (node (ref "U1") (pin "61") (pinfunction "VSS_7_61") (pintype "power_in"))
      (node (ref "U1") (pin "71") (pinfunction "VSS_1_71") (pintype "power_in"))
      (node (ref "U1") (pin "83") (pinfunction "VSS_8_83") (pintype "power_in"))
      (node (ref "U1") (pin "94") (pinfunction "VSS_9_94") (pintype "power_in"))
      (node (ref "U2") (pin "7") (pinfunction "GND_7") (pintype "power_in"))
      (node (ref "UART1") (pin "2") (pinfunction "2_2") (pintype "passive"))
      (node (ref "WH_DIR") (pin "2") (pinfunction "2_2") (pintype "passive"))
      (node (ref "WH_EN") (pin "3") (pinfunction "3_3") (pintype "passive"))
      (node (ref "WH_SP") (pin "3") (pinfunction "3_3") (pintype "passive"))
    )
    (net (code "66") (name "Net-(D1-K)") (class "Default")
      (node (ref "D1") (pin "2") (pinfunction "K_2") (pintype "passive"))
      (node (ref "L1") (pin "1") (pinfunction "1_1") (pintype "passive"))
      (node (ref "LM2") (pin "2") (pinfunction "OUT_2") (pintype "power_in"))
    )
    (net (code "67") (name "Net-(ENCODER-Pad1)") (class "Default")
      (node (ref "ENCODER") (pin "1") (pinfunction "1_1") (pintype "passive"))
      (node (ref "R29") (pin "1") (pinfunction "1_1") (pintype "passive"))
    )
    (net (code "68") (name "Net-(ENCODER-Pad2)") (class "Default")
      (node (ref "ENCODER") (pin "2") (pinfunction "2_2") (pintype "passive"))
      (node (ref "R28") (pin "1") (pinfunction "1_1") (pintype "passive"))
    )
    (net (code "69") (name "Net-(ENCODER-Pad3)") (class "Default")
      (node (ref "ENCODER") (pin "3") (pinfunction "3_3") (pintype "passive"))
      (node (ref "R23") (pin "1") (pinfunction "1_1") (pintype "passive"))
    )
    (net (code "70") (name "Net-(ENCODER-Pad4)") (class "Default")
      (node (ref "ENCODER") (pin "4") (pinfunction "4_4") (pintype "passive"))
      (node (ref "R22") (pin "1") (pinfunction "1_1") (pintype "passive"))
    )
    (net (code "71") (name "Net-(F1-Pad1)") (class "Default")
      (node (ref "F1") (pin "1") (pinfunction "1_1") (pintype "passive"))
      (node (ref "RD_IN") (pin "2") (pinfunction "2_2") (pintype "passive"))
    )
    (net (code "72") (name "Net-(LED1-A)") (class "Default")
      (node (ref "LED1") (pin "1") (pinfunction "A_1") (pintype "passive"))
      (node (ref "R6") (pin "1") (pinfunction "1_1") (pintype "passive"))
    )
    (net (code "73") (name "Net-(LED2-A)") (class "Default")
      (node (ref "LED2") (pin "1") (pinfunction "A_1") (pintype "passive"))
      (node (ref "R7") (pin "1") (pinfunction "1_1") (pintype "passive"))
    )
    (net (code "74") (name "Net-(R1-Pad2)") (class "Default")
      (node (ref "R1") (pin "2") (pinfunction "2_2") (pintype "passive"))
      (node (ref "R3") (pin "1") (pinfunction "1_1") (pintype "passive"))
      (node (ref "R4") (pin "2") (pinfunction "2_2") (pintype "passive"))
    )
    (net (code "75") (name "Net-(R2-Pad1)") (class "Default")
      (node (ref "R2") (pin "1") (pinfunction "1_1") (pintype "passive"))
      (node (ref "R3") (pin "2") (pinfunction "2_2") (pintype "passive"))
    )
    (net (code "76") (name "Net-(SW1-NC1)") (class "Default")
      (node (ref "CC1") (pin "1") (pinfunction "1_1") (pintype "passive"))
      (node (ref "FU1") (pin "1") (pinfunction "1_1") (pintype "passive"))
      (node (ref "SW1") (pin "1") (pinfunction "NC1_1") (pintype "passive"))
      (node (ref "SW1") (pin "4") (pinfunction "NO2_4") (pintype "passive"))
    )
    (net (code "77") (name "Net-(U2-Pad3)") (class "Default")
      (node (ref "U2") (pin "3") (pintype "output"))
      (node (ref "U2") (pin "4") (pintype "input"))
    )
    (net (code "78") (name "Net-(U2-Pad12)") (class "Default")
      (node (ref "U2") (pin "12") (pintype "input"))
      (node (ref "U2") (pin "8") (pintype "output"))
    )
    (net (code "79") (name "PGND") (class "Default")
      (node (ref "24V_1") (pin "2") (pinfunction "2_2") (pintype "passive"))
      (node (ref "24V_2") (pin "2") (pinfunction "2_2") (pintype "passive"))
      (node (ref "24V_3") (pin "2") (pinfunction "2_2") (pintype "passive"))
      (node (ref "24V_4") (pin "2") (pinfunction "2_2") (pintype "passive"))
      (node (ref "CC1") (pin "2") (pinfunction "2_2") (pintype "passive"))
      (node (ref "CON1") (pin "2") (pintype "power_in"))
      (node (ref "L3") (pin "2") (pinfunction "2_2") (pintype "passive"))
      (node (ref "L4") (pin "1") (pinfunction "1_1") (pintype "passive"))
      (node (ref "Motor1") (pin "5") (pinfunction "5_5") (pintype "passive"))
      (node (ref "Motor2") (pin "5") (pinfunction "5_5") (pintype "passive"))
      (node (ref "Motor3") (pin "5") (pinfunction "5_5") (pintype "passive"))
      (node (ref "Motor4") (pin "5") (pinfunction "5_5") (pintype "passive"))
      (node (ref "R4") (pin "1") (pinfunction "1_1") (pintype "passive"))
      (node (ref "RD_IN") (pin "1") (pinfunction "1_1") (pintype "passive"))
      (node (ref "TX1") (pin "1") (pinfunction "-_1") (pintype "passive"))
    )
    (net (code "80") (name "VDDA") (class "Default")
      (node (ref "C7") (pin "2") (pinfunction "2_2") (pintype "passive"))
      (node (ref "C8") (pin "2") (pinfunction "2_2") (pintype "passive"))
      (node (ref "L2") (pin "2") (pinfunction "2_2") (pintype "passive"))
      (node (ref "U1") (pin "32") (pinfunction "VREF+_32") (pintype "power_in"))
      (node (ref "U1") (pin "33") (pinfunction "VDDA_33") (pintype "power_in"))
    )
    (net (code "81") (name "unconnected-(CON1-Pad0)") (class "Default")
      (node (ref "CON1") (pin "0") (pintype "power_in"))
    )
    (net (code "82") (name "unconnected-(JP1-Pad2)") (class "Default")
      (node (ref "JP1") (pin "2") (pinfunction "2_2") (pintype "passive"))
    )
    (net (code "83") (name "unconnected-(SW1-COM2-Pad2)") (class "Default")
      (node (ref "SW1") (pin "2") (pinfunction "COM2_2") (pintype "passive"))
    )
    (net (code "84") (name "unconnected-(SW1-COM2-Pad5)") (class "Default")
      (node (ref "SW1") (pin "5") (pinfunction "COM2_5") (pintype "passive"))
    )
    (net (code "85") (name "unconnected-(U1A-PA5-Pad41)") (class "Default")
      (node (ref "U1") (pin "41") (pinfunction "PA5_41") (pintype "bidirectional"))
    )
    (net (code "86") (name "unconnected-(U1A-PA12-Pad104)") (class "Default")
      (node (ref "U1") (pin "104") (pinfunction "PA12_104") (pintype "bidirectional"))
    )
    (net (code "87") (name "unconnected-(U1A-PA15-Pad110)") (class "Default")
      (node (ref "U1") (pin "110") (pinfunction "PA15_110") (pintype "bidirectional"))
    )
    (net (code "88") (name "unconnected-(U1A-PB3-Pad133)") (class "Default")
      (node (ref "U1") (pin "133") (pinfunction "PB3_133") (pintype "bidirectional"))
    )
    (net (code "89") (name "unconnected-(U1A-PB4-Pad134)") (class "Default")
      (node (ref "U1") (pin "134") (pinfunction "PB4_134") (pintype "bidirectional"))
    )
    (net (code "90") (name "unconnected-(U1A-PB5-Pad135)") (class "Default")
      (node (ref "U1") (pin "135") (pinfunction "PB5_135") (pintype "bidirectional"))
    )
    (net (code "91") (name "unconnected-(U1A-PB8-Pad139)") (class "Default")
      (node (ref "U1") (pin "139") (pinfunction "PB8_139") (pintype "bidirectional"))
    )
    (net (code "92") (name "unconnected-(U1A-PB9-Pad140)") (class "Default")
      (node (ref "U1") (pin "140") (pinfunction "PB9_140") (pintype "bidirectional"))
    )
    (net (code "93") (name "unconnected-(U1A-PB12-Pad73)") (class "Default")
      (node (ref "U1") (pin "73") (pinfunction "PB12_73") (pintype "bidirectional"))
    )
    (net (code "94") (name "unconnected-(U1A-PB13-Pad74)") (class "Default")
      (node (ref "U1") (pin "74") (pinfunction "PB13_74") (pintype "bidirectional"))
    )
    (net (code "95") (name "unconnected-(U1A-PB14-Pad75)") (class "Default")
      (node (ref "U1") (pin "75") (pinfunction "PB14_75") (pintype "bidirectional"))
    )
    (net (code "96") (name "unconnected-(U1A-PB15-Pad76)") (class "Default")
      (node (ref "U1") (pin "76") (pinfunction "PB15_76") (pintype "bidirectional"))
    )
    (net (code "97") (name "unconnected-(U1A-PC1-Pad27)") (class "Default")
      (node (ref "U1") (pin "27") (pinfunction "PC1_27") (pintype "bidirectional"))
    )
    (net (code "98") (name "unconnected-(U1A-PC4-Pad44)") (class "Default")
      (node (ref "U1") (pin "44") (pinfunction "PC4_44") (pintype "bidirectional"))
    )
    (net (code "99") (name "unconnected-(U1A-PC8-Pad98)") (class "Default")
      (node (ref "U1") (pin "98") (pinfunction "PC8_98") (pintype "bidirectional"))
    )
    (net (code "100") (name "unconnected-(U1A-PC9-Pad99)") (class "Default")
      (node (ref "U1") (pin "99") (pinfunction "PC9_99") (pintype "bidirectional"))
    )
    (net (code "101") (name "unconnected-(U1A-PC10-Pad111)") (class "Default")
      (node (ref "U1") (pin "111") (pinfunction "PC10_111") (pintype "bidirectional"))
    )
    (net (code "102") (name "unconnected-(U1A-PC11-Pad112)") (class "Default")
      (node (ref "U1") (pin "112") (pinfunction "PC11_112") (pintype "bidirectional"))
    )
    (net (code "103") (name "unconnected-(U1A-PC12-Pad113)") (class "Default")
      (node (ref "U1") (pin "113") (pinfunction "PC12_113") (pintype "bidirectional"))
    )
    (net (code "104") (name "unconnected-(U1A-PC13-TAMPER-RTC-Pad7)") (class "Default")
      (node (ref "U1") (pin "7") (pinfunction "PC13-TAMPER-RTC_7") (pintype "bidirectional"))
    )
    (net (code "105") (name "unconnected-(U1A-PC14-OSC32_IN-Pad8)") (class "Default")
      (node (ref "U1") (pin "8") (pinfunction "PC14-OSC32_IN_8") (pintype "bidirectional"))
    )
    (net (code "106") (name "unconnected-(U1A-PC15-OSC32_OUT-Pad9)") (class "Default")
      (node (ref "U1") (pin "9") (pinfunction "PC15-OSC32_OUT_9") (pintype "bidirectional"))
    )
    (net (code "107") (name "unconnected-(U1A-PD0-Pad114)") (class "Default")
      (node (ref "U1") (pin "114") (pinfunction "PD0_114") (pintype "bidirectional"))
    )
    (net (code "108") (name "unconnected-(U1A-PD1-Pad115)") (class "Default")
      (node (ref "U1") (pin "115") (pinfunction "PD1_115") (pintype "bidirectional"))
    )
    (net (code "109") (name "unconnected-(U1A-PD2-Pad116)") (class "Default")
      (node (ref "U1") (pin "116") (pinfunction "PD2_116") (pintype "bidirectional"))
    )
    (net (code "110") (name "unconnected-(U1A-PD3-Pad117)") (class "Default")
      (node (ref "U1") (pin "117") (pinfunction "PD3_117") (pintype "bidirectional"))
    )
    (net (code "111") (name "unconnected-(U1A-PD4-Pad118)") (class "Default")
      (node (ref "U1") (pin "118") (pinfunction "PD4_118") (pintype "bidirectional"))
    )
    (net (code "112") (name "unconnected-(U1A-PD5-Pad119)") (class "Default")
      (node (ref "U1") (pin "119") (pinfunction "PD5_119") (pintype "bidirectional"))
    )
    (net (code "113") (name "unconnected-(U1A-PD6-Pad122)") (class "Default")
      (node (ref "U1") (pin "122") (pinfunction "PD6_122") (pintype "bidirectional"))
    )
    (net (code "114") (name "unconnected-(U1A-PD7-Pad123)") (class "Default")
      (node (ref "U1") (pin "123") (pinfunction "PD7_123") (pintype "bidirectional"))
    )
    (net (code "115") (name "unconnected-(U1A-PD8-Pad77)") (class "Default")
      (node (ref "U1") (pin "77") (pinfunction "PD8_77") (pintype "bidirectional"))
    )
    (net (code "116") (name "unconnected-(U1A-PD14-Pad85)") (class "Default")
      (node (ref "U1") (pin "85") (pinfunction "PD14_85") (pintype "bidirectional"))
    )
    (net (code "117") (name "unconnected-(U1A-PD15-Pad86)") (class "Default")
      (node (ref "U1") (pin "86") (pinfunction "PD15_86") (pintype "bidirectional"))
    )
    (net (code "118") (name "unconnected-(U1B-NC-Pad106)") (class "Default")
      (node (ref "U1") (pin "106") (pinfunction "NC_106") (pintype "passive"))
    )
    (net (code "119") (name "unconnected-(U1B-PE0-Pad141)") (class "Default")
      (node (ref "U1") (pin "141") (pinfunction "PE0_141") (pintype "bidirectional"))
    )
    (net (code "120") (name "unconnected-(U1B-PE1-Pad142)") (class "Default")
      (node (ref "U1") (pin "142") (pinfunction "PE1_142") (pintype "bidirectional"))
    )
    (net (code "121") (name "unconnected-(U1B-PE2-Pad1)") (class "Default")
      (node (ref "U1") (pin "1") (pinfunction "PE2_1") (pintype "bidirectional"))
    )
    (net (code "122") (name "unconnected-(U1B-PE3-Pad2)") (class "Default")
      (node (ref "U1") (pin "2") (pinfunction "PE3_2") (pintype "bidirectional"))
    )
    (net (code "123") (name "unconnected-(U1B-PE4-Pad3)") (class "Default")
      (node (ref "U1") (pin "3") (pinfunction "PE4_3") (pintype "bidirectional"))
    )
    (net (code "124") (name "unconnected-(U1B-PE5-Pad4)") (class "Default")
      (node (ref "U1") (pin "4") (pinfunction "PE5_4") (pintype "bidirectional"))
    )
    (net (code "125") (name "unconnected-(U1B-PE6-Pad5)") (class "Default")
      (node (ref "U1") (pin "5") (pinfunction "PE6_5") (pintype "bidirectional"))
    )
    (net (code "126") (name "unconnected-(U1B-PE7-Pad58)") (class "Default")
      (node (ref "U1") (pin "58") (pinfunction "PE7_58") (pintype "bidirectional"))
    )
    (net (code "127") (name "unconnected-(U1B-PE8-Pad59)") (class "Default")
      (node (ref "U1") (pin "59") (pinfunction "PE8_59") (pintype "bidirectional"))
    )
    (net (code "128") (name "unconnected-(U1B-PE9-Pad60)") (class "Default")
      (node (ref "U1") (pin "60") (pinfunction "PE9_60") (pintype "bidirectional"))
    )
    (net (code "129") (name "unconnected-(U1B-PE10-Pad63)") (class "Default")
      (node (ref "U1") (pin "63") (pinfunction "PE10_63") (pintype "bidirectional"))
    )
    (net (code "130") (name "unconnected-(U1B-PE11-Pad64)") (class "Default")
      (node (ref "U1") (pin "64") (pinfunction "PE11_64") (pintype "bidirectional"))
    )
    (net (code "131") (name "unconnected-(U1B-PE12-Pad65)") (class "Default")
      (node (ref "U1") (pin "65") (pinfunction "PE12_65") (pintype "bidirectional"))
    )
    (net (code "132") (name "unconnected-(U1B-PE13-Pad66)") (class "Default")
      (node (ref "U1") (pin "66") (pinfunction "PE13_66") (pintype "bidirectional"))
    )
    (net (code "133") (name "unconnected-(U1B-PE14-Pad67)") (class "Default")
      (node (ref "U1") (pin "67") (pinfunction "PE14_67") (pintype "bidirectional"))
    )
    (net (code "134") (name "unconnected-(U1B-PE15-Pad68)") (class "Default")
      (node (ref "U1") (pin "68") (pinfunction "PE15_68") (pintype "bidirectional"))
    )
    (net (code "135") (name "unconnected-(U1B-PF0-Pad10)") (class "Default")
      (node (ref "U1") (pin "10") (pinfunction "PF0_10") (pintype "bidirectional"))
    )
    (net (code "136") (name "unconnected-(U1B-PF1-Pad11)") (class "Default")
      (node (ref "U1") (pin "11") (pinfunction "PF1_11") (pintype "bidirectional"))
    )
    (net (code "137") (name "unconnected-(U1B-PF2-Pad12)") (class "Default")
      (node (ref "U1") (pin "12") (pinfunction "PF2_12") (pintype "bidirectional"))
    )
    (net (code "138") (name "unconnected-(U1B-PF3-Pad13)") (class "Default")
      (node (ref "U1") (pin "13") (pinfunction "PF3_13") (pintype "bidirectional"))
    )
    (net (code "139") (name "unconnected-(U1B-PF4-Pad14)") (class "Default")
      (node (ref "U1") (pin "14") (pinfunction "PF4_14") (pintype "bidirectional"))
    )
    (net (code "140") (name "unconnected-(U1B-PF8-Pad20)") (class "Default")
      (node (ref "U1") (pin "20") (pinfunction "PF8_20") (pintype "bidirectional"))
    )
    (net (code "141") (name "unconnected-(U1B-PF9-Pad21)") (class "Default")
      (node (ref "U1") (pin "21") (pinfunction "PF9_21") (pintype "bidirectional"))
    )
    (net (code "142") (name "unconnected-(U1B-PF10-Pad22)") (class "Default")
      (node (ref "U1") (pin "22") (pinfunction "PF10_22") (pintype "bidirectional"))
    )
    (net (code "143") (name "unconnected-(U1B-PF15-Pad55)") (class "Default")
      (node (ref "U1") (pin "55") (pinfunction "PF15_55") (pintype "bidirectional"))
    )
    (net (code "144") (name "unconnected-(U1B-PG11-Pad126)") (class "Default")
      (node (ref "U1") (pin "126") (pinfunction "PG11_126") (pintype "bidirectional"))
    )
    (net (code "145") (name "unconnected-(U1B-PG12-Pad127)") (class "Default")
      (node (ref "U1") (pin "127") (pinfunction "PG12_127") (pintype "bidirectional"))
    )
    (net (code "146") (name "unconnected-(U1B-PG13-Pad128)") (class "Default")
      (node (ref "U1") (pin "128") (pinfunction "PG13_128") (pintype "bidirectional"))
    )
    (net (code "147") (name "unconnected-(U1B-PG14-Pad129)") (class "Default")
      (node (ref "U1") (pin "129") (pinfunction "PG14_129") (pintype "bidirectional"))
    )
    (net (code "148") (name "unconnected-(U1B-PG15-Pad132)") (class "Default")
      (node (ref "U1") (pin "132") (pinfunction "PG15_132") (pintype "bidirectional"))
    )
    (net (code "149") (name "unconnected-(WH_EN-Pad1)") (class "Default")
      (node (ref "WH_EN") (pin "1") (pinfunction "1_1") (pintype "passive"))
    )
    (net (code "150") (name "unconnected-(WH_SP-Pad1)") (class "Default")
      (node (ref "WH_SP") (pin "1") (pinfunction "1_1") (pintype "passive"))
    )
  )
)
